# IR-Blue_BT4_PCB.net
KiCad netlist of a schematic drawn in EAGLE
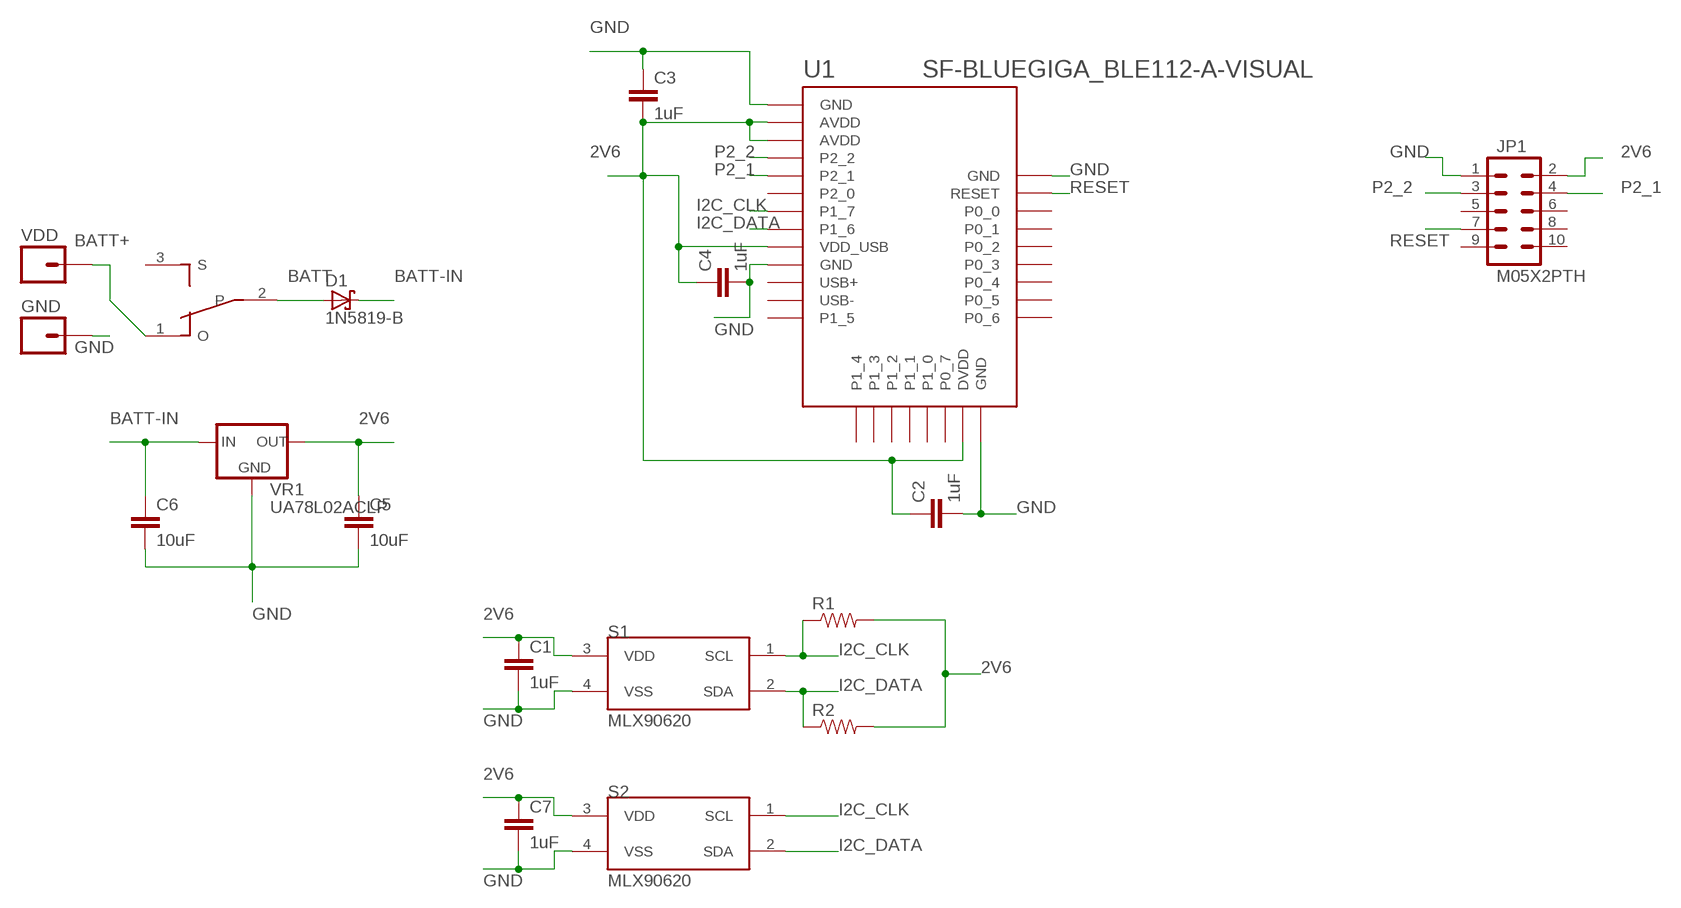
[diagram p0: schematic, sheet 1]

(export (version "E")
  (design (tool "Eeschema 10.0.6"))
  (components
    (comp (ref "C1")
      (value "1uF")
      (footprint "eagle-import:CAP-PTH-5MM")
      (libsource (lib "eagle-import") (part "CAPPTH1"))
    )
    (comp (ref "C2")
      (value "1uF")
      (footprint "eagle-import:CAP-PTH-5MM")
      (libsource (lib "eagle-import") (part "CAPPTH1"))
    )
    (comp (ref "C3")
      (value "1uF")
      (footprint "eagle-import:CAP-PTH-5MM")
      (libsource (lib "eagle-import") (part "CAPPTH1"))
    )
    (comp (ref "C4")
      (value "1uF")
      (footprint "eagle-import:CAP-PTH-5MM")
      (libsource (lib "eagle-import") (part "CAPPTH1"))
    )
    (comp (ref "C5")
      (value "10uF")
      (footprint "eagle-import:CAP-PTH-5MM")
      (libsource (lib "eagle-import") (part "CAPPTH1"))
    )
    (comp (ref "C6")
      (value "10uF")
      (footprint "eagle-import:CAP-PTH-5MM")
      (libsource (lib "eagle-import") (part "CAPPTH1"))
    )
    (comp (ref "C7")
      (value "1uF")
      (footprint "eagle-import:CAP-PTH-5MM")
      (libsource (lib "eagle-import") (part "CAPPTH1"))
    )
    (comp (ref "D1")
      (value "1N5819-B")
      (footprint "eagle-import:DO41-7.6")
      (libsource (lib "eagle-import") (part "1N5819-B"))
    )
    (comp (ref "GND")
      (value "M01PTH")
      (footprint "eagle-import:1X01")
      (libsource (lib "eagle-import") (part "M01PTH"))
    )
    (comp (ref "JP1")
      (value "M05X2PTH")
      (footprint "eagle-import:AVR_ICSP")
      (libsource (lib "eagle-import") (part "M05X2PTH"))
    )
    (comp (ref "R1")
      (value "RESISTORPTH-1/4W")
      (footprint "eagle-import:AXIAL-0.4")
      (libsource (lib "eagle-import") (part "RESISTORPTH-1/4W"))
    )
    (comp (ref "R2")
      (value "RESISTORPTH-1/4W")
      (footprint "eagle-import:AXIAL-0.4")
      (libsource (lib "eagle-import") (part "RESISTORPTH-1/4W"))
    )
    (comp (ref "S1")
      (value "MLX90620")
      (footprint "eagle-import:TO-39")
      (libsource (lib "eagle-import") (part "MLX90620"))
    )
    (comp (ref "S2")
      (value "MLX90620")
      (footprint "eagle-import:TO-39")
      (libsource (lib "eagle-import") (part "MLX90620"))
    )
    (comp (ref "SW1")
      (value "SMALL_SWITCH")
      (footprint "eagle-import:EG1213")
      (libsource (lib "eagle-import") (part "SMALL_SWITCH"))
    )
    (comp (ref "U1")
      (value "SF-BLUEGIGA_BLE112-A-VISUAL")
      (footprint "eagle-import:SF-BLUEGIGA_BLE112-A")
      (libsource (lib "eagle-import") (part "SF-BLUEGIGA_BLE112-A-VISUAL"))
    )
    (comp (ref "VDD")
      (value "M01PTH")
      (footprint "eagle-import:1X01")
      (libsource (lib "eagle-import") (part "M01PTH"))
    )
    (comp (ref "VR1")
      (value "UA78L02ACLP")
      (footprint "eagle-import:TO-92")
      (libsource (lib "eagle-import") (part "2V6-VREG"))
    )
  )
  (nets
    (net (code "1") (name "/2V6") (class "Default")
      (node (ref "C1") (pin "1") (pinfunction "1_1") (pintype "passive"))
      (node (ref "C2") (pin "1") (pinfunction "1_1") (pintype "passive"))
      (node (ref "C3") (pin "2") (pinfunction "2_2") (pintype "passive"))
      (node (ref "C4") (pin "1") (pinfunction "1_1") (pintype "passive"))
      (node (ref "C5") (pin "1") (pinfunction "1_1") (pintype "passive"))
      (node (ref "C7") (pin "1") (pinfunction "1_1") (pintype "passive"))
      (node (ref "JP1") (pin "2") (pinfunction "2_2") (pintype "passive"))
      (node (ref "R1") (pin "P$2") (pinfunction "2_P$2") (pintype "passive"))
      (node (ref "R2") (pin "P$2") (pinfunction "2_P$2") (pintype "passive"))
      (node (ref "S1") (pin "3") (pinfunction "VDD_3") (pintype "bidirectional"))
      (node (ref "S2") (pin "3") (pinfunction "VDD_3") (pintype "bidirectional"))
      (node (ref "U1") (pin "AVDD1") (pinfunction "AVDD_AVDD1") (pintype "power_in"))
      (node (ref "U1") (pin "AVDD2") (pinfunction "AVDD_AVDD2") (pintype "power_in"))
      (node (ref "U1") (pin "DVDD") (pinfunction "DVDD_DVDD") (pintype "power_in"))
      (node (ref "U1") (pin "VDD_USB") (pinfunction "VDD_USB_VDD_USB") (pintype "power_in"))
      (node (ref "VR1") (pin "1") (pinfunction "OUT_1") (pintype "output"))
    )
    (net (code "2") (name "/BATT") (class "Default")
      (node (ref "D1") (pin "A") (pinfunction "A_A") (pintype "passive"))
      (node (ref "SW1") (pin "2") (pinfunction "P_2") (pintype "bidirectional"))
    )
    (net (code "3") (name "/BATT+") (class "Default")
      (node (ref "SW1") (pin "1") (pinfunction "O_1") (pintype "bidirectional"))
      (node (ref "VDD") (pin "1") (pinfunction "1_1") (pintype "passive"))
    )
    (net (code "4") (name "/BATT-IN") (class "Default")
      (node (ref "C6") (pin "1") (pinfunction "1_1") (pintype "passive"))
      (node (ref "D1") (pin "C") (pinfunction "C_C") (pintype "passive"))
      (node (ref "VR1") (pin "3") (pinfunction "IN_3") (pintype "input"))
    )
    (net (code "5") (name "/GND") (class "Default")
      (node (ref "C1") (pin "2") (pinfunction "2_2") (pintype "passive"))
      (node (ref "C2") (pin "2") (pinfunction "2_2") (pintype "passive"))
      (node (ref "C3") (pin "1") (pinfunction "1_1") (pintype "passive"))
      (node (ref "C4") (pin "2") (pinfunction "2_2") (pintype "passive"))
      (node (ref "C5") (pin "2") (pinfunction "2_2") (pintype "passive"))
      (node (ref "C6") (pin "2") (pinfunction "2_2") (pintype "passive"))
      (node (ref "C7") (pin "2") (pinfunction "2_2") (pintype "passive"))
      (node (ref "GND") (pin "1") (pinfunction "1_1") (pintype "passive"))
      (node (ref "JP1") (pin "1") (pinfunction "1_1") (pintype "passive"))
      (node (ref "S1") (pin "4") (pinfunction "VSS_4") (pintype "bidirectional"))
      (node (ref "S2") (pin "4") (pinfunction "VSS_4") (pintype "bidirectional"))
      (node (ref "U1") (pin "GND1") (pinfunction "GND_GND1") (pintype "power_in"))
      (node (ref "U1") (pin "GND2") (pinfunction "GND_GND2") (pintype "power_in"))
      (node (ref "U1") (pin "GND3") (pinfunction "GND_GND3") (pintype "power_in"))
      (node (ref "U1") (pin "GND4") (pinfunction "GND_GND4") (pintype "power_in"))
      (node (ref "VR1") (pin "2") (pinfunction "GND_2") (pintype "input"))
    )
    (net (code "6") (name "/I2C_CLK") (class "Default")
      (node (ref "R1") (pin "P$1") (pinfunction "1_P$1") (pintype "passive"))
      (node (ref "S1") (pin "1") (pinfunction "SCL_1") (pintype "bidirectional"))
      (node (ref "S2") (pin "1") (pinfunction "SCL_1") (pintype "bidirectional"))
      (node (ref "U1") (pin "P1_7") (pinfunction "P1_7_P1_7") (pintype "bidirectional"))
    )
    (net (code "7") (name "/I2C_DATA") (class "Default")
      (node (ref "R2") (pin "P$1") (pinfunction "1_P$1") (pintype "passive"))
      (node (ref "S1") (pin "2") (pinfunction "SDA_2") (pintype "bidirectional"))
      (node (ref "S2") (pin "2") (pinfunction "SDA_2") (pintype "bidirectional"))
      (node (ref "U1") (pin "P1_6") (pinfunction "P1_6_P1_6") (pintype "bidirectional"))
    )
    (net (code "8") (name "/P2_1") (class "Default")
      (node (ref "JP1") (pin "4") (pinfunction "4_4") (pintype "passive"))
      (node (ref "U1") (pin "P2_1") (pinfunction "P2_1_P2_1") (pintype "bidirectional"))
    )
    (net (code "9") (name "/P2_2") (class "Default")
      (node (ref "JP1") (pin "3") (pinfunction "3_3") (pintype "passive"))
      (node (ref "U1") (pin "P2_2") (pinfunction "P2_2_P2_2") (pintype "bidirectional"))
    )
    (net (code "10") (name "/RESET") (class "Default")
      (node (ref "JP1") (pin "7") (pinfunction "7_7") (pintype "passive"))
      (node (ref "U1") (pin "RESET") (pinfunction "RESET_RESET") (pintype "input"))
    )
    (net (code "11") (name "unconnected-(JP1-Pad5)") (class "Default")
      (node (ref "JP1") (pin "5") (pinfunction "5_5") (pintype "passive"))
    )
    (net (code "12") (name "unconnected-(JP1-Pad6)") (class "Default")
      (node (ref "JP1") (pin "6") (pinfunction "6_6") (pintype "passive"))
    )
    (net (code "13") (name "unconnected-(JP1-Pad8)") (class "Default")
      (node (ref "JP1") (pin "8") (pinfunction "8_8") (pintype "passive"))
    )
    (net (code "14") (name "unconnected-(JP1-Pad9)") (class "Default")
      (node (ref "JP1") (pin "9") (pinfunction "9_9") (pintype "passive"))
    )
    (net (code "15") (name "unconnected-(JP1-Pad10)") (class "Default")
      (node (ref "JP1") (pin "10") (pinfunction "10_10") (pintype "passive"))
    )
    (net (code "16") (name "unconnected-(SW1-S-Pad3)") (class "Default")
      (node (ref "SW1") (pin "3") (pinfunction "S_3") (pintype "bidirectional"))
    )
    (net (code "17") (name "unconnected-(U1-PadP0_0)") (class "Default")
      (node (ref "U1") (pin "P0_0") (pinfunction "P0_0_P0_0") (pintype "bidirectional"))
    )
    (net (code "18") (name "unconnected-(U1-PadP0_1)") (class "Default")
      (node (ref "U1") (pin "P0_1") (pinfunction "P0_1_P0_1") (pintype "bidirectional"))
    )
    (net (code "19") (name "unconnected-(U1-PadP0_2)") (class "Default")
      (node (ref "U1") (pin "P0_2") (pinfunction "P0_2_P0_2") (pintype "bidirectional"))
    )
    (net (code "20") (name "unconnected-(U1-PadP0_3)") (class "Default")
      (node (ref "U1") (pin "P0_3") (pinfunction "P0_3_P0_3") (pintype "bidirectional"))
    )
    (net (code "21") (name "unconnected-(U1-PadP0_4)") (class "Default")
      (node (ref "U1") (pin "P0_4") (pinfunction "P0_4_P0_4") (pintype "bidirectional"))
    )
    (net (code "22") (name "unconnected-(U1-PadP0_5)") (class "Default")
      (node (ref "U1") (pin "P0_5") (pinfunction "P0_5_P0_5") (pintype "bidirectional"))
    )
    (net (code "23") (name "unconnected-(U1-PadP0_6)") (class "Default")
      (node (ref "U1") (pin "P0_6") (pinfunction "P0_6_P0_6") (pintype "bidirectional"))
    )
    (net (code "24") (name "unconnected-(U1-PadP0_7)") (class "Default")
      (node (ref "U1") (pin "P0_7") (pinfunction "P0_7_P0_7") (pintype "bidirectional"))
    )
    (net (code "25") (name "unconnected-(U1-PadP1_0)") (class "Default")
      (node (ref "U1") (pin "P1_0") (pinfunction "P1_0_P1_0") (pintype "bidirectional"))
    )
    (net (code "26") (name "unconnected-(U1-PadP1_1)") (class "Default")
      (node (ref "U1") (pin "P1_1") (pinfunction "P1_1_P1_1") (pintype "bidirectional"))
    )
    (net (code "27") (name "unconnected-(U1-PadP1_2)") (class "Default")
      (node (ref "U1") (pin "P1_2") (pinfunction "P1_2_P1_2") (pintype "bidirectional"))
    )
    (net (code "28") (name "unconnected-(U1-PadP1_3)") (class "Default")
      (node (ref "U1") (pin "P1_3") (pinfunction "P1_3_P1_3") (pintype "bidirectional"))
    )
    (net (code "29") (name "unconnected-(U1-PadP1_4)") (class "Default")
      (node (ref "U1") (pin "P1_4") (pinfunction "P1_4_P1_4") (pintype "bidirectional"))
    )
    (net (code "30") (name "unconnected-(U1-PadP1_5)") (class "Default")
      (node (ref "U1") (pin "P1_5") (pinfunction "P1_5_P1_5") (pintype "bidirectional"))
    )
    (net (code "31") (name "unconnected-(U1-PadP2_0)") (class "Default")
      (node (ref "U1") (pin "P2_0") (pinfunction "P2_0_P2_0") (pintype "bidirectional"))
    )
    (net (code "32") (name "unconnected-(U1-PadUSB+)") (class "Default")
      (node (ref "U1") (pin "USB+") (pinfunction "USB+_USB+") (pintype "bidirectional"))
    )
    (net (code "33") (name "unconnected-(U1-PadUSB-)") (class "Default")
      (node (ref "U1") (pin "USB-") (pinfunction "USB-_USB-") (pintype "bidirectional"))
    )
  )
)
